# uC_Main_3.net
KiCad netlist of a schematic drawn in EAGLE
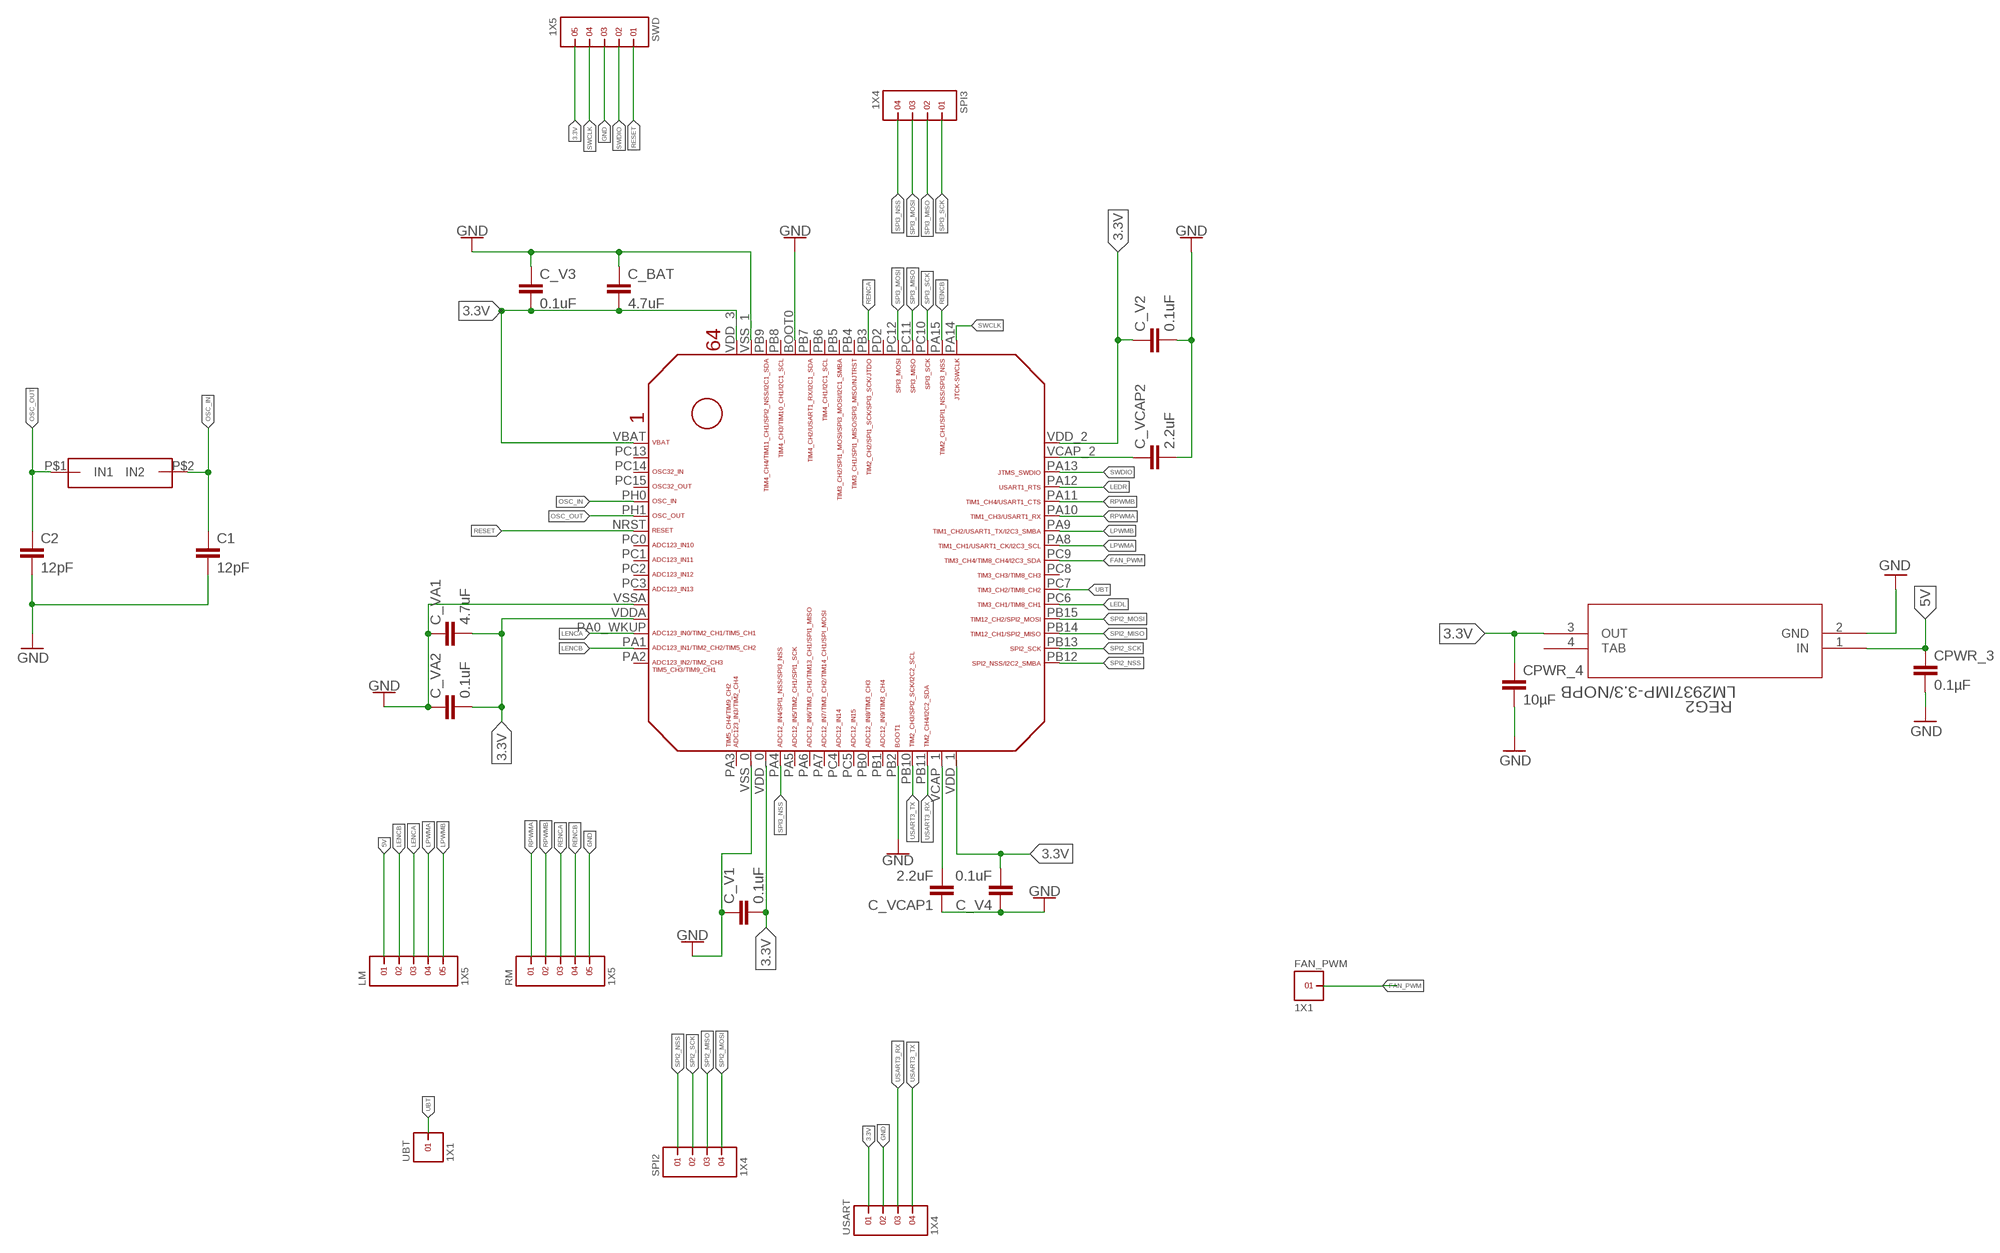
[diagram p0: schematic, sheet 1]

(export (version "E")
  (design (tool "Eeschema 10.0.6"))
  (components
    (comp (ref "C1")
      (value "12pF")
      (footprint "eagle-import:0603")
      (libsource (lib "eagle-import") (part "22PF-0603-50V-5%"))
    )
    (comp (ref "C2")
      (value "12pF")
      (footprint "eagle-import:0603")
      (libsource (lib "eagle-import") (part "22PF-0603-50V-5%"))
    )
    (comp (ref "CPWR_3")
      (value "0.1µF")
      (footprint "eagle-import:0805")
      (libsource (lib "eagle-import") (part "0.33UF/330NF-0805-50V-10%"))
    )
    (comp (ref "CPWR_4")
      (value "10µF")
      (footprint "eagle-import:0805")
      (libsource (lib "eagle-import") (part "0.33UF/330NF-0805-50V-10%"))
    )
    (comp (ref "C_BAT")
      (value "4.7uF")
      (footprint "eagle-import:0805@1")
      (libsource (lib "eagle-import") (part "22UF-0805-6.3V-20%"))
    )
    (comp (ref "C_V1")
      (value "0.1uF")
      (footprint "eagle-import:0805@1")
      (libsource (lib "eagle-import") (part "22UF-0805-6.3V-20%"))
    )
    (comp (ref "C_V2")
      (value "0.1uF")
      (footprint "eagle-import:0805@1")
      (libsource (lib "eagle-import") (part "22UF-0805-6.3V-20%"))
    )
    (comp (ref "C_V3")
      (value "0.1uF")
      (footprint "eagle-import:0805@1")
      (libsource (lib "eagle-import") (part "22UF-0805-6.3V-20%"))
    )
    (comp (ref "C_V4")
      (value "0.1uF")
      (footprint "eagle-import:0805@1")
      (libsource (lib "eagle-import") (part "22UF-0805-6.3V-20%"))
    )
    (comp (ref "C_VA1")
      (value "4.7uF")
      (footprint "eagle-import:0805@1")
      (libsource (lib "eagle-import") (part "22UF-0805-6.3V-20%"))
    )
    (comp (ref "C_VA2")
      (value "0.1uF")
      (footprint "eagle-import:0805@1")
      (libsource (lib "eagle-import") (part "22UF-0805-6.3V-20%"))
    )
    (comp (ref "C_VCAP1")
      (value "2.2uF")
      (footprint "eagle-import:0805@1")
      (libsource (lib "eagle-import") (part "22UF-0805-6.3V-20%"))
    )
    (comp (ref "C_VCAP2")
      (value "2.2uF")
      (footprint "eagle-import:0805@1")
      (libsource (lib "eagle-import") (part "22UF-0805-6.3V-20%"))
    )
    (comp (ref "FAN_PWM")
      (value "1X1")
      (footprint "eagle-import:1X1")
      (libsource (lib "eagle-import") (part "1X1"))
    )
    (comp (ref "LM")
      (value "1X5")
      (footprint "eagle-import:1X5")
      (libsource (lib "eagle-import") (part "1X5"))
    )
    (comp (ref "REG2")
      (value "LM2937IMP-3.3/NOPB")
      (footprint "eagle-import:MP04A")
      (fields
        (field (name "MANUFACTURER_PART_NUMBER") "lm2937imp3_3nopb")
        (field (name "COPYRIGHT") "Copyright C 2015 Accelerated Designs. All rights reserved")
      )
      (libsource (lib "eagle-import") (part "LM2937IMP-3.3/NOPB"))
    )
    (comp (ref "RM")
      (value "1X5")
      (footprint "eagle-import:1X5")
      (libsource (lib "eagle-import") (part "1X5"))
    )
    (comp (ref "SPI2")
      (value "1X4")
      (footprint "eagle-import:1X4")
      (libsource (lib "eagle-import") (part "1X4"))
    )
    (comp (ref "SPI3")
      (value "1X4")
      (footprint "eagle-import:1X4")
      (libsource (lib "eagle-import") (part "1X4"))
    )
    (comp (ref "SWD")
      (value "1X5")
      (footprint "eagle-import:1X5")
      (libsource (lib "eagle-import") (part "1X5"))
    )
    (comp (ref "U$1")
      (value "STM32F405/415_LQFP64")
      (footprint "eagle-import:STM32F405_415_LQFP64")
      (libsource (lib "eagle-import") (part "STM32F405/415_LQFP64"))
    )
    (comp (ref "U$2")
      (value "OSC")
      (footprint "eagle-import:OSC")
      (libsource (lib "eagle-import") (part "OSC"))
    )
    (comp (ref "UBT")
      (value "1X1")
      (footprint "eagle-import:1X1")
      (libsource (lib "eagle-import") (part "1X1"))
    )
    (comp (ref "USART")
      (value "1X4")
      (footprint "eagle-import:1X4")
      (libsource (lib "eagle-import") (part "1X4"))
    )
  )
  (nets
    (net (code "1") (name "/TAB") (class "Default")
      (node (ref "REG2") (pin "4") (pinfunction "TAB_4") (pintype "power_in"))
    )
    (net (code "2") (name "3.3V") (class "Default")
      (node (ref "CPWR_4") (pin "1") (pinfunction "1_1") (pintype "passive"))
      (node (ref "C_BAT") (pin "2") (pinfunction "2_2") (pintype "passive"))
      (node (ref "C_V1") (pin "2") (pinfunction "2_2") (pintype "passive"))
      (node (ref "C_V2") (pin "1") (pinfunction "1_1") (pintype "passive"))
      (node (ref "C_V3") (pin "2") (pinfunction "2_2") (pintype "passive"))
      (node (ref "C_V4") (pin "2") (pinfunction "2_2") (pintype "passive"))
      (node (ref "C_VA1") (pin "2") (pinfunction "2_2") (pintype "passive"))
      (node (ref "C_VA2") (pin "2") (pinfunction "2_2") (pintype "passive"))
      (node (ref "REG2") (pin "3") (pinfunction "OUT_3") (pintype "power_in"))
      (node (ref "SWD") (pin "5") (pinfunction "5_5") (pintype "bidirectional"))
      (node (ref "U$1") (pin "VBAT") (pinfunction "VBAT_VBAT") (pintype "bidirectional"))
      (node (ref "U$1") (pin "VDDA") (pinfunction "VDDA_VDDA") (pintype "bidirectional"))
      (node (ref "U$1") (pin "VDD_0") (pinfunction "VDD_0_VDD_0") (pintype "bidirectional"))
      (node (ref "U$1") (pin "VDD_1") (pinfunction "VDD_1_VDD_1") (pintype "bidirectional"))
      (node (ref "U$1") (pin "VDD_2") (pinfunction "VDD_2_VDD_2") (pintype "bidirectional"))
      (node (ref "U$1") (pin "VDD_3") (pinfunction "VDD_3_VDD_3") (pintype "bidirectional"))
      (node (ref "USART") (pin "1") (pinfunction "1_1") (pintype "bidirectional"))
    )
    (net (code "3") (name "5V") (class "Default")
      (node (ref "CPWR_3") (pin "1") (pinfunction "1_1") (pintype "passive"))
      (node (ref "LM") (pin "1") (pinfunction "1_1") (pintype "bidirectional"))
      (node (ref "REG2") (pin "1") (pinfunction "IN_1") (pintype "power_in"))
    )
    (net (code "4") (name "FAN_PWM") (class "Default")
      (node (ref "FAN_PWM") (pin "1") (pinfunction "1_1") (pintype "bidirectional"))
      (node (ref "U$1") (pin "PC9") (pinfunction "PC9_PC9") (pintype "bidirectional"))
    )
    (net (code "5") (name "GND") (class "Default")
      (node (ref "C1") (pin "2") (pinfunction "2_2") (pintype "passive"))
      (node (ref "C2") (pin "2") (pinfunction "2_2") (pintype "passive"))
      (node (ref "CPWR_3") (pin "2") (pinfunction "2_2") (pintype "passive"))
      (node (ref "CPWR_4") (pin "2") (pinfunction "2_2") (pintype "passive"))
      (node (ref "C_BAT") (pin "1") (pinfunction "1_1") (pintype "passive"))
      (node (ref "C_V1") (pin "1") (pinfunction "1_1") (pintype "passive"))
      (node (ref "C_V2") (pin "2") (pinfunction "2_2") (pintype "passive"))
      (node (ref "C_V3") (pin "1") (pinfunction "1_1") (pintype "passive"))
      (node (ref "C_V4") (pin "1") (pinfunction "1_1") (pintype "passive"))
      (node (ref "C_VA1") (pin "1") (pinfunction "1_1") (pintype "passive"))
      (node (ref "C_VA2") (pin "1") (pinfunction "1_1") (pintype "passive"))
      (node (ref "C_VCAP1") (pin "1") (pinfunction "1_1") (pintype "passive"))
      (node (ref "C_VCAP2") (pin "2") (pinfunction "2_2") (pintype "passive"))
      (node (ref "REG2") (pin "2") (pinfunction "GND_2") (pintype "power_in"))
      (node (ref "RM") (pin "5") (pinfunction "5_5") (pintype "bidirectional"))
      (node (ref "SWD") (pin "3") (pinfunction "3_3") (pintype "bidirectional"))
      (node (ref "U$1") (pin "BOOT0") (pinfunction "BOOT0_BOOT0") (pintype "bidirectional"))
      (node (ref "U$1") (pin "PB2") (pinfunction "PB2_PB2") (pintype "bidirectional"))
      (node (ref "U$1") (pin "VSSA") (pinfunction "VSSA_VSSA") (pintype "bidirectional"))
      (node (ref "U$1") (pin "VSS_0") (pinfunction "VSS_0_VSS_0") (pintype "bidirectional"))
      (node (ref "U$1") (pin "VSS_1") (pinfunction "VSS_1_VSS_1") (pintype "bidirectional"))
      (node (ref "USART") (pin "2") (pinfunction "2_2") (pintype "bidirectional"))
    )
    (net (code "6") (name "LEDL") (class "Default")
      (node (ref "U$1") (pin "PC6") (pinfunction "PC6_PC6") (pintype "bidirectional"))
    )
    (net (code "7") (name "LEDR") (class "Default")
      (node (ref "U$1") (pin "PA12") (pinfunction "PA12_PA12") (pintype "bidirectional"))
    )
    (net (code "8") (name "LENCA") (class "Default")
      (node (ref "LM") (pin "3") (pinfunction "3_3") (pintype "bidirectional"))
      (node (ref "U$1") (pin "PA0_WKUP") (pinfunction "PA0_AKUP_PA0_WKUP") (pintype "bidirectional"))
    )
    (net (code "9") (name "LENCB") (class "Default")
      (node (ref "LM") (pin "2") (pinfunction "2_2") (pintype "bidirectional"))
      (node (ref "U$1") (pin "PA1") (pinfunction "PA1_PA1") (pintype "bidirectional"))
    )
    (net (code "10") (name "LPWMA") (class "Default")
      (node (ref "LM") (pin "4") (pinfunction "4_4") (pintype "bidirectional"))
      (node (ref "U$1") (pin "PA8") (pinfunction "PA8_PA8") (pintype "bidirectional"))
    )
    (net (code "11") (name "LPWMB") (class "Default")
      (node (ref "LM") (pin "5") (pinfunction "5_5") (pintype "bidirectional"))
      (node (ref "U$1") (pin "PA9") (pinfunction "PA9_PA9") (pintype "bidirectional"))
    )
    (net (code "12") (name "Net-(C_VCAP1-Pad2)") (class "Default")
      (node (ref "C_VCAP1") (pin "2") (pinfunction "2_2") (pintype "passive"))
      (node (ref "U$1") (pin "VCAP_1") (pinfunction "VCAP_1_VCAP_1") (pintype "bidirectional"))
    )
    (net (code "13") (name "Net-(C_VCAP2-Pad1)") (class "Default")
      (node (ref "C_VCAP2") (pin "1") (pinfunction "1_1") (pintype "passive"))
      (node (ref "U$1") (pin "VCAP_2") (pinfunction "VCAP_2_VCAP_2") (pintype "bidirectional"))
    )
    (net (code "14") (name "OSC_IN") (class "Default")
      (node (ref "C1") (pin "1") (pinfunction "1_1") (pintype "passive"))
      (node (ref "U$1") (pin "PH0") (pinfunction "PH0_PH0") (pintype "bidirectional"))
      (node (ref "U$2") (pin "P$2") (pinfunction "IN2_P$2") (pintype "bidirectional"))
    )
    (net (code "15") (name "OSC_OUT") (class "Default")
      (node (ref "C2") (pin "1") (pinfunction "1_1") (pintype "passive"))
      (node (ref "U$1") (pin "PH1") (pinfunction "PH1_PH1") (pintype "bidirectional"))
      (node (ref "U$2") (pin "P$1") (pinfunction "IN1_P$1") (pintype "bidirectional"))
    )
    (net (code "16") (name "RENCA") (class "Default")
      (node (ref "RM") (pin "3") (pinfunction "3_3") (pintype "bidirectional"))
      (node (ref "U$1") (pin "PB3") (pinfunction "PB3_PB3") (pintype "bidirectional"))
    )
    (net (code "17") (name "RENCB") (class "Default")
      (node (ref "RM") (pin "4") (pinfunction "4_4") (pintype "bidirectional"))
      (node (ref "U$1") (pin "PA15") (pinfunction "PA15_PA15") (pintype "bidirectional"))
    )
    (net (code "18") (name "RESET") (class "Default")
      (node (ref "SWD") (pin "1") (pinfunction "1_1") (pintype "bidirectional"))
      (node (ref "U$1") (pin "NRST") (pinfunction "NRST_NRST") (pintype "bidirectional"))
    )
    (net (code "19") (name "RPWMA") (class "Default")
      (node (ref "RM") (pin "1") (pinfunction "1_1") (pintype "bidirectional"))
      (node (ref "U$1") (pin "PA10") (pinfunction "PA10_PA10") (pintype "bidirectional"))
    )
    (net (code "20") (name "RPWMB") (class "Default")
      (node (ref "RM") (pin "2") (pinfunction "2_2") (pintype "bidirectional"))
      (node (ref "U$1") (pin "PA11") (pinfunction "PA11_PA11") (pintype "bidirectional"))
    )
    (net (code "21") (name "SPI2_MISO") (class "Default")
      (node (ref "SPI2") (pin "3") (pinfunction "3_3") (pintype "bidirectional"))
      (node (ref "U$1") (pin "PB14") (pinfunction "PB14_PB14") (pintype "bidirectional"))
    )
    (net (code "22") (name "SPI2_MOSI") (class "Default")
      (node (ref "SPI2") (pin "4") (pinfunction "4_4") (pintype "bidirectional"))
      (node (ref "U$1") (pin "PB15") (pinfunction "PB15_PB15") (pintype "bidirectional"))
    )
    (net (code "23") (name "SPI2_NSS") (class "Default")
      (node (ref "SPI2") (pin "1") (pinfunction "1_1") (pintype "bidirectional"))
      (node (ref "U$1") (pin "PB12") (pinfunction "PB12_PB12") (pintype "bidirectional"))
    )
    (net (code "24") (name "SPI2_SCK") (class "Default")
      (node (ref "SPI2") (pin "2") (pinfunction "2_2") (pintype "bidirectional"))
      (node (ref "U$1") (pin "PB13") (pinfunction "PB13_PB13") (pintype "bidirectional"))
    )
    (net (code "25") (name "SPI3_MISO") (class "Default")
      (node (ref "SPI3") (pin "2") (pinfunction "2_2") (pintype "bidirectional"))
      (node (ref "U$1") (pin "PC11") (pinfunction "PC11_PC11") (pintype "bidirectional"))
    )
    (net (code "26") (name "SPI3_MOSI") (class "Default")
      (node (ref "SPI3") (pin "3") (pinfunction "3_3") (pintype "bidirectional"))
      (node (ref "U$1") (pin "PC12") (pinfunction "PC12_PC12") (pintype "bidirectional"))
    )
    (net (code "27") (name "SPI3_NSS") (class "Default")
      (node (ref "SPI3") (pin "4") (pinfunction "4_4") (pintype "bidirectional"))
      (node (ref "U$1") (pin "PA4") (pinfunction "PA4_PA4") (pintype "bidirectional"))
    )
    (net (code "28") (name "SPI3_SCK") (class "Default")
      (node (ref "SPI3") (pin "1") (pinfunction "1_1") (pintype "bidirectional"))
      (node (ref "U$1") (pin "PC10") (pinfunction "PC10_PC10") (pintype "bidirectional"))
    )
    (net (code "29") (name "SWCLK") (class "Default")
      (node (ref "SWD") (pin "4") (pinfunction "4_4") (pintype "bidirectional"))
      (node (ref "U$1") (pin "PA14") (pinfunction "PA14_PA14") (pintype "bidirectional"))
    )
    (net (code "30") (name "SWDIO") (class "Default")
      (node (ref "SWD") (pin "2") (pinfunction "2_2") (pintype "bidirectional"))
      (node (ref "U$1") (pin "PA13") (pinfunction "PA13_PA13") (pintype "bidirectional"))
    )
    (net (code "31") (name "UBT") (class "Default")
      (node (ref "U$1") (pin "PC7") (pinfunction "PC7_PC7") (pintype "bidirectional"))
      (node (ref "UBT") (pin "1") (pinfunction "1_1") (pintype "bidirectional"))
    )
    (net (code "32") (name "USART3_RX") (class "Default")
      (node (ref "U$1") (pin "PB11") (pinfunction "PB11_PB11") (pintype "bidirectional"))
      (node (ref "USART") (pin "3") (pinfunction "3_3") (pintype "bidirectional"))
    )
    (net (code "33") (name "USART3_TX") (class "Default")
      (node (ref "U$1") (pin "PB10") (pinfunction "PB10_PB10") (pintype "bidirectional"))
      (node (ref "USART") (pin "4") (pinfunction "4_4") (pintype "bidirectional"))
    )
    (net (code "34") (name "unconnected-(U$1-PadPA2)") (class "Default")
      (node (ref "U$1") (pin "PA2") (pinfunction "PA2_PA2") (pintype "bidirectional"))
    )
    (net (code "35") (name "unconnected-(U$1-PadPA3)") (class "Default")
      (node (ref "U$1") (pin "PA3") (pinfunction "PA3_PA3") (pintype "bidirectional"))
    )
    (net (code "36") (name "unconnected-(U$1-PadPA5)") (class "Default")
      (node (ref "U$1") (pin "PA5") (pinfunction "PA5_PA5") (pintype "bidirectional"))
    )
    (net (code "37") (name "unconnected-(U$1-PadPA6)") (class "Default")
      (node (ref "U$1") (pin "PA6") (pinfunction "PA6_PA6") (pintype "bidirectional"))
    )
    (net (code "38") (name "unconnected-(U$1-PadPA7)") (class "Default")
      (node (ref "U$1") (pin "PA7") (pinfunction "PA7_PA7") (pintype "bidirectional"))
    )
    (net (code "39") (name "unconnected-(U$1-PadPB0)") (class "Default")
      (node (ref "U$1") (pin "PB0") (pinfunction "PB0_PB0") (pintype "bidirectional"))
    )
    (net (code "40") (name "unconnected-(U$1-PadPB1)") (class "Default")
      (node (ref "U$1") (pin "PB1") (pinfunction "PB1_PB1") (pintype "bidirectional"))
    )
    (net (code "41") (name "unconnected-(U$1-PadPB4)") (class "Default")
      (node (ref "U$1") (pin "PB4") (pinfunction "PB4_PB4") (pintype "bidirectional"))
    )
    (net (code "42") (name "unconnected-(U$1-PadPB5)") (class "Default")
      (node (ref "U$1") (pin "PB5") (pinfunction "PB5_PB5") (pintype "bidirectional"))
    )
    (net (code "43") (name "unconnected-(U$1-PadPB6)") (class "Default")
      (node (ref "U$1") (pin "PB6") (pinfunction "PB6_PB6") (pintype "bidirectional"))
    )
    (net (code "44") (name "unconnected-(U$1-PadPB7)") (class "Default")
      (node (ref "U$1") (pin "PB7") (pinfunction "PB7_PB7") (pintype "bidirectional"))
    )
    (net (code "45") (name "unconnected-(U$1-PadPB8)") (class "Default")
      (node (ref "U$1") (pin "PB8") (pinfunction "PB8_PB8") (pintype "bidirectional"))
    )
    (net (code "46") (name "unconnected-(U$1-PadPB9)") (class "Default")
      (node (ref "U$1") (pin "PB9") (pinfunction "PB9_PB9") (pintype "bidirectional"))
    )
    (net (code "47") (name "unconnected-(U$1-PadPC0)") (class "Default")
      (node (ref "U$1") (pin "PC0") (pinfunction "PC0_PC0") (pintype "bidirectional"))
    )
    (net (code "48") (name "unconnected-(U$1-PadPC1)") (class "Default")
      (node (ref "U$1") (pin "PC1") (pinfunction "PC1_PC1") (pintype "bidirectional"))
    )
    (net (code "49") (name "unconnected-(U$1-PadPC2)") (class "Default")
      (node (ref "U$1") (pin "PC2") (pinfunction "PC2_PC2") (pintype "bidirectional"))
    )
    (net (code "50") (name "unconnected-(U$1-PadPC3)") (class "Default")
      (node (ref "U$1") (pin "PC3") (pinfunction "PC3_PC3") (pintype "bidirectional"))
    )
    (net (code "51") (name "unconnected-(U$1-PadPC4)") (class "Default")
      (node (ref "U$1") (pin "PC4") (pinfunction "PC4_PC4") (pintype "bidirectional"))
    )
    (net (code "52") (name "unconnected-(U$1-PadPC5)") (class "Default")
      (node (ref "U$1") (pin "PC5") (pinfunction "PC5_PC5") (pintype "bidirectional"))
    )
    (net (code "53") (name "unconnected-(U$1-PadPC8)") (class "Default")
      (node (ref "U$1") (pin "PC8") (pinfunction "PC8_PC8") (pintype "bidirectional"))
    )
    (net (code "54") (name "unconnected-(U$1-PadPC13)") (class "Default")
      (node (ref "U$1") (pin "PC13") (pinfunction "PC13_PC13") (pintype "bidirectional"))
    )
    (net (code "55") (name "unconnected-(U$1-PadPC14)") (class "Default")
      (node (ref "U$1") (pin "PC14") (pinfunction "PC14_PC14") (pintype "bidirectional"))
    )
    (net (code "56") (name "unconnected-(U$1-PadPC15)") (class "Default")
      (node (ref "U$1") (pin "PC15") (pinfunction "PC15_PC15") (pintype "bidirectional"))
    )
    (net (code "57") (name "unconnected-(U$1-PadPD2)") (class "Default")
      (node (ref "U$1") (pin "PD2") (pinfunction "PD2_PD2") (pintype "bidirectional"))
    )
  )
)
